# Power.net
KiCad netlist of a schematic drawn in Altium Designer
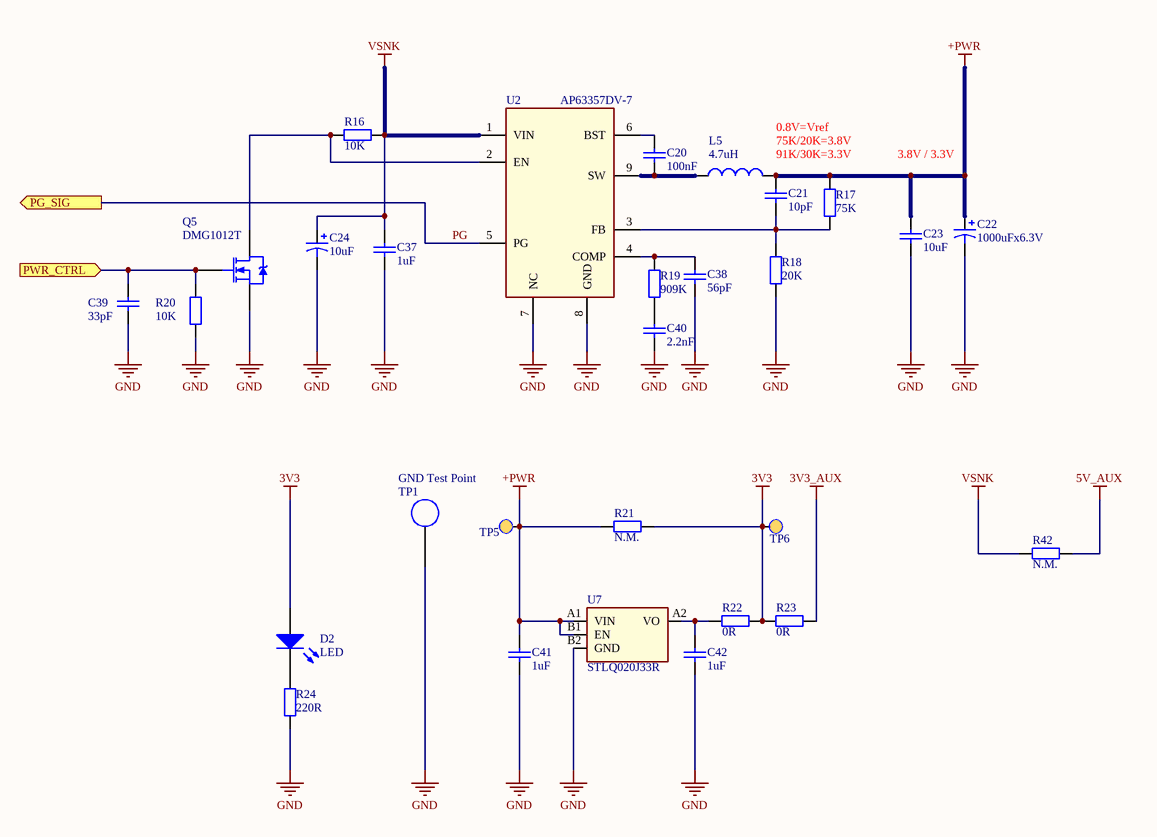
[diagram p0: Power.SchDoc]

(export (version "E")
  (design (tool "Eeschema 10.0.6"))
  (components
    (comp (ref "C20")
      (value "100nF")
      (footprint "C0402")
      (description "Capacitor (Semiconductor SIM Model)")
      (fields
        (field (name "MANUFACTURER") "YAGEO")
        (field (name "MANUFACTURER PART NO.") "CC0402KRX7R9BB104")
      )
      (libsource (lib "Miscellaneous Devices") (part "Cap Semi"))
    )
    (comp (ref "C21")
      (value "10pF")
      (footprint "C0402")
      (description "Capacitor (Semiconductor SIM Model)")
      (fields
        (field (name "MANUFACTURER") "YAGEO")
        (field (name "MANUFACTURER PART NO.") "CC0402JRNPO9BN100")
      )
      (libsource (lib "Miscellaneous Devices") (part "Cap Semi"))
    )
    (comp (ref "C22")
      (value "1000uFx6.3V")
      (footprint "7361-38")
      (fields
        (field (name "MANUFACTURER") "AVX")
        (field (name "MANUFACTURER PART NO.") "TPSV108M006R0050")
        (field (name "Comment") "electrolytic capacitor")
      )
      (libsource (lib "Miscellaneous Devices") (part "Cap Pol1"))
    )
    (comp (ref "C23")
      (value "10uF")
      (footprint "C0402")
      (description "Capacitor (Semiconductor SIM Model)")
      (fields
        (field (name "MANUFACTURER") "Samsung Electronics")
        (field (name "MANUFACTURER PART NO.") "CL05A106MP5NUNC")
      )
      (libsource (lib "Miscellaneous Devices") (part "Cap Semi"))
    )
    (comp (ref "C24")
      (value "10uF")
      (footprint "Case-B")
      (fields
        (field (name "MANUFACTURER") "AVX")
        (field (name "MANUFACTURER PART NO.") "TCJB106M025R0100")
        (field (name "Comment") "electrolytic capacitor")
      )
      (libsource (lib "Miscellaneous Devices") (part "Cap Pol1"))
    )
    (comp (ref "C37")
      (value "1uF")
      (footprint "C0402")
      (description "Capacitor (Semiconductor SIM Model)")
      (fields
        (field (name "MANUFACTURER") "muRata")
        (field (name "MANUFACTURER PART NO.") "GRM155R61E105KA12D")
      )
      (libsource (lib "Miscellaneous Devices") (part "Cap Semi"))
    )
    (comp (ref "C38")
      (value "56pF")
      (footprint "C0402")
      (description "Capacitor (Semiconductor SIM Model)")
      (fields
        (field (name "MANUFACTURER") "YAGEO")
        (field (name "MANUFACTURER PART NO.") "CC0402JRNPO9BN560")
      )
      (libsource (lib "Miscellaneous Devices") (part "Cap Semi"))
    )
    (comp (ref "C39")
      (value "33pF")
      (footprint "C0402")
      (description "Capacitor (Semiconductor SIM Model)")
      (fields (field (name "MANUFACTURER") "AVX") (field (name "MANUFACTURER PART NO.") "04025A330JAT2A"))
      (libsource (lib "Miscellaneous Devices") (part "Cap Semi"))
    )
    (comp (ref "C40")
      (value "2.2nF")
      (footprint "C0402")
      (description "Capacitor (Semiconductor SIM Model)")
      (fields
        (field (name "MANUFACTURER") "YAGEO")
        (field (name "MANUFACTURER PART NO.") "CC0402KPX7R9BB222")
      )
      (libsource (lib "Miscellaneous Devices") (part "Cap Semi"))
    )
    (comp (ref "C41")
      (value "1uF")
      (footprint "C0402")
      (description "Capacitor (Semiconductor SIM Model)")
      (fields
        (field (name "MANUFACTURER") "muRata")
        (field (name "MANUFACTURER PART NO.") "GRM155R61E105KA12D")
      )
      (libsource (lib "Miscellaneous Devices") (part "Cap Semi"))
    )
    (comp (ref "C42")
      (value "1uF")
      (footprint "C0402")
      (description "Capacitor (Semiconductor SIM Model)")
      (fields
        (field (name "MANUFACTURER") "muRata")
        (field (name "MANUFACTURER PART NO.") "GRM155R61E105KA12D")
      )
      (libsource (lib "Miscellaneous Devices") (part "Cap Semi"))
    )
    (comp (ref "D2")
      (value "LED")
      (footprint "PICOLED")
      (description "Typical SMD LED")
      (fields
        (field (name "MANUFACTURER") "OSRAM")
        (field (name "MANUFACTURER PART NO.") "LTQH9G-Q2OO-25-2Z4Y-5-R18")
      )
      (libsource (lib "Miscellaneous Devices") (part "LED2"))
    )
    (comp (ref "L5")
      (value "4.7uH")
      (footprint "CHILSIN_5.4x5.7")
      (description "Inductor")
      (fields
        (field (name "MANUFACTURER") "CHILISIN")
        (field (name "MANUFACTURER PART NO.") "BMRA000505204R7MA1")
      )
      (libsource (lib "Miscellaneous Devices") (part "Inductor"))
    )
    (comp (ref "Q5")
      (value "DMG1012T")
      (footprint "SOT-523_custom")
      (description "N-Channel Power MOSFET")
      (fields (field (name "MANUFACTURER") "Diodes Inc.") (field (name "MANUFACTURER PART NO.") "DMG1012T-7"))
      (libsource (lib "Miscellaneous Devices") (part "NMOS-2"))
    )
    (comp (ref "R16")
      (value "10K")
      (footprint "R0402")
      (fields
        (field (name "MANUFACTURER") "ASJ")
        (field (name "MANUFACTURER PART NO.") "CR10-103-JK")
        (field (name "Comment") "Res2")
      )
      (libsource (lib "") (part "Res2_3"))
    )
    (comp (ref "R17")
      (value "75K")
      (footprint "R0402")
      (fields
        (field (name "MANUFACTURER") "YAGEO")
        (field (name "MANUFACTURER PART NO.") "RC0402JR-0775KL")
        (field (name "Comment") "Res2")
      )
      (libsource (lib "Miscellaneous Devices") (part "Res2"))
    )
    (comp (ref "R18")
      (value "20K")
      (footprint "R0402")
      (fields
        (field (name "MANUFACTURER") "YAGEO")
        (field (name "MANUFACTURER PART NO.") "AC0402JR-0720KL")
        (field (name "Comment") "Res2")
      )
      (libsource (lib "Miscellaneous Devices") (part "Res2"))
    )
    (comp (ref "R19")
      (value "909K")
      (footprint "R0402")
      (fields
        (field (name "MANUFACTURER") "ASJ")
        (field (name "MANUFACTURER PART NO.") "RC0402FR-07909KL")
        (field (name "Comment") "Res2")
      )
      (libsource (lib "Miscellaneous Devices") (part "Res2"))
    )
    (comp (ref "R20")
      (value "10K")
      (footprint "R0402")
      (fields
        (field (name "MANUFACTURER") "ASJ")
        (field (name "MANUFACTURER PART NO.") "CR10-103-JK")
        (field (name "Comment") "Res2")
      )
      (libsource (lib "") (part "Res2_2"))
    )
    (comp (ref "R21")
      (value "N.M.")
      (footprint "R0402")
      (fields
        (field (name "MANUFACTURER") "YAGEO")
        (field (name "MANUFACTURER PART NO.") "RC0402FR-070RL")
        (field (name "Comment") "Res2")
      )
      (libsource (lib "") (part "Res2_1"))
    )
    (comp (ref "R22")
      (value "0R")
      (footprint "R0402")
      (fields
        (field (name "MANUFACTURER") "YAGEO")
        (field (name "MANUFACTURER PART NO.") "RC0402FR-070RL")
        (field (name "Comment") "Res2")
      )
      (libsource (lib "") (part "Res2_1"))
    )
    (comp (ref "R23")
      (value "0R")
      (footprint "R0402")
      (fields
        (field (name "MANUFACTURER") "YAGEO")
        (field (name "MANUFACTURER PART NO.") "RC0402FR-070RL")
        (field (name "Comment") "Res2")
      )
      (libsource (lib "") (part "Res2_1"))
    )
    (comp (ref "R24")
      (value "220R")
      (footprint "R0402")
      (fields
        (field (name "MANUFACTURER") "ASJ")
        (field (name "MANUFACTURER PART NO.") "CR10-221-JK")
        (field (name "Comment") "Res2")
      )
      (libsource (lib "Miscellaneous Devices") (part "Res2"))
    )
    (comp (ref "R42")
      (value "N.M.")
      (footprint "R1206")
      (fields
        (field (name "MANUFACTURER") "YAGEO")
        (field (name "MANUFACTURER PART NO.") "RC0402FR-070RL")
        (field (name "Comment") "Res2")
      )
      (libsource (lib "") (part "Res2_1"))
    )
    (comp (ref "TP1")
      (value "GND Test Point")
      (footprint "5019_keystone")
      (description "SMD Test Point")
      (fields
        (field (name "MANUFACTURER") "Keystone Electrincs")
        (field (name "MANUFACTURER PART NO.") "5019")
      )
      (libsource (lib "test_point") (part "5019"))
    )
    (comp (ref "TP5")
      (value "Test_Point")
      (footprint "TEST_POINT")
      (description "Test Point")
      (libsource (lib "Test Point") (part "Test_Point"))
    )
    (comp (ref "TP6")
      (value "Test_Point")
      (footprint "TEST_POINT")
      (description "Test Point")
      (libsource (lib "Test Point") (part "Test_Point"))
    )
    (comp (ref "U2")
      (value "AP63357DV-7")
      (footprint "V-DFN3020-13")
      (description "3.8V TO 32VINPUT, 3.5A Low IQ Synchronous Buck with Enhanced EMI Reduction")
      (fields (field (name "MANUFACTURER") "Diodes Inc."))
      (libsource (lib "AP63356") (part "AP63356"))
    )
    (comp (ref "U7")
      (value "STLQ020J33R")
      (footprint "Flip-Chip4")
      (description "LDO")
      (fields (field (name "MANUFACTURER") "STMicroelectronics"))
      (libsource (lib "RUTLEO") (part "STLQ020"))
    )
  )
  (nets
    (net (code "1") (name "+PWR") (class "Default")
      (node (ref "C21") (pin "2") (pinfunction "2_2") (pintype "passive"))
      (node (ref "C22") (pin "1") (pinfunction "1_1") (pintype "passive"))
      (node (ref "C23") (pin "2") (pinfunction "2_2") (pintype "passive"))
      (node (ref "C41") (pin "1") (pinfunction "1_1") (pintype "passive"))
      (node (ref "L5") (pin "2") (pinfunction "2_2") (pintype "passive"))
      (node (ref "R17") (pin "1") (pinfunction "1_1") (pintype "passive"))
      (node (ref "R21") (pin "2") (pinfunction "2_2") (pintype "passive"))
      (node (ref "TP5") (pin "0") (pinfunction "0_0") (pintype "passive"))
      (node (ref "U7") (pin "A1") (pinfunction "VIN_A1") (pintype "passive"))
      (node (ref "U7") (pin "B1") (pinfunction "EN_B1") (pintype "passive"))
    )
    (net (code "2") (name "/PG") (class "Default")
      (node (ref "U2") (pin "5") (pinfunction "PG_5") (pintype "passive"))
    )
    (net (code "3") (name "/PWR_CTRL") (class "Default")
      (node (ref "C39") (pin "1") (pinfunction "1_1") (pintype "passive"))
      (node (ref "Q5") (pin "1") (pinfunction "G_1") (pintype "passive"))
      (node (ref "R20") (pin "2") (pinfunction "2_2") (pintype "passive"))
    )
    (net (code "4") (name "3V3") (class "Default")
      (node (ref "D2") (pin "1") (pinfunction "A_1") (pintype "passive"))
      (node (ref "R21") (pin "1") (pinfunction "1_1") (pintype "passive"))
      (node (ref "R22") (pin "1") (pinfunction "1_1") (pintype "passive"))
      (node (ref "R23") (pin "2") (pinfunction "2_2") (pintype "passive"))
      (node (ref "TP6") (pin "0") (pinfunction "0_0") (pintype "passive"))
    )
    (net (code "5") (name "3V3_AUX") (class "Default")
      (node (ref "R23") (pin "1") (pinfunction "1_1") (pintype "passive"))
    )
    (net (code "6") (name "5V_AUX") (class "Default")
      (node (ref "R42") (pin "1") (pinfunction "1_1") (pintype "passive"))
    )
    (net (code "7") (name "GND") (class "Default")
      (node (ref "C22") (pin "2") (pinfunction "2_2") (pintype "passive"))
      (node (ref "C23") (pin "1") (pinfunction "1_1") (pintype "passive"))
      (node (ref "C24") (pin "2") (pinfunction "2_2") (pintype "passive"))
      (node (ref "C37") (pin "1") (pinfunction "1_1") (pintype "passive"))
      (node (ref "C38") (pin "1") (pinfunction "1_1") (pintype "passive"))
      (node (ref "C39") (pin "2") (pinfunction "2_2") (pintype "passive"))
      (node (ref "C40") (pin "1") (pinfunction "1_1") (pintype "passive"))
      (node (ref "C41") (pin "2") (pinfunction "2_2") (pintype "passive"))
      (node (ref "C42") (pin "2") (pinfunction "2_2") (pintype "passive"))
      (node (ref "Q5") (pin "3") (pinfunction "S_3") (pintype "passive"))
      (node (ref "R18") (pin "2") (pinfunction "2_2") (pintype "passive"))
      (node (ref "R20") (pin "1") (pinfunction "1_1") (pintype "passive"))
      (node (ref "R24") (pin "2") (pinfunction "2_2") (pintype "passive"))
      (node (ref "TP1") (pin "1") (pinfunction "1_1") (pintype "passive"))
      (node (ref "U2") (pin "7") (pinfunction "NC_7") (pintype "passive"))
      (node (ref "U2") (pin "8") (pinfunction "GND_8") (pintype "passive"))
      (node (ref "U7") (pin "B2") (pinfunction "GND_B2") (pintype "passive"))
    )
    (net (code "8") (name "Net-(C40-Pad2)") (class "Default")
      (node (ref "C40") (pin "2") (pinfunction "2_2") (pintype "passive"))
      (node (ref "R19") (pin "2") (pinfunction "2_2") (pintype "passive"))
    )
    (net (code "9") (name "Net-(D2-K)") (class "Default")
      (node (ref "D2") (pin "2") (pinfunction "K_2") (pintype "passive"))
      (node (ref "R24") (pin "1") (pinfunction "1_1") (pintype "passive"))
    )
    (net (code "10") (name "Net-(Q5-D)") (class "Default")
      (node (ref "Q5") (pin "2") (pinfunction "D_2") (pintype "passive"))
      (node (ref "R16") (pin "1") (pinfunction "1_1") (pintype "passive"))
      (node (ref "U2") (pin "2") (pinfunction "EN_2") (pintype "passive"))
    )
    (net (code "11") (name "Net-(U2-BST)") (class "Default")
      (node (ref "C20") (pin "1") (pinfunction "1_1") (pintype "passive"))
      (node (ref "U2") (pin "6") (pinfunction "BST_6") (pintype "passive"))
    )
    (net (code "12") (name "Net-(U2-COMP)") (class "Default")
      (node (ref "C38") (pin "2") (pinfunction "2_2") (pintype "passive"))
      (node (ref "R19") (pin "1") (pinfunction "1_1") (pintype "passive"))
      (node (ref "U2") (pin "4") (pinfunction "COMP_4") (pintype "passive"))
    )
    (net (code "13") (name "Net-(U2-FB)") (class "Default")
      (node (ref "C21") (pin "1") (pinfunction "1_1") (pintype "passive"))
      (node (ref "R17") (pin "2") (pinfunction "2_2") (pintype "passive"))
      (node (ref "R18") (pin "1") (pinfunction "1_1") (pintype "passive"))
      (node (ref "U2") (pin "3") (pinfunction "FB_3") (pintype "passive"))
    )
    (net (code "14") (name "Net-(U2-SW)") (class "Default")
      (node (ref "C20") (pin "2") (pinfunction "2_2") (pintype "passive"))
      (node (ref "L5") (pin "1") (pinfunction "1_1") (pintype "passive"))
      (node (ref "U2") (pin "9") (pinfunction "SW_9") (pintype "passive"))
    )
    (net (code "15") (name "Net-(U7-VO)") (class "Default")
      (node (ref "C42") (pin "1") (pinfunction "1_1") (pintype "passive"))
      (node (ref "R22") (pin "2") (pinfunction "2_2") (pintype "passive"))
      (node (ref "U7") (pin "A2") (pinfunction "VO_A2") (pintype "passive"))
    )
    (net (code "16") (name "VSNK") (class "Default")
      (node (ref "C24") (pin "1") (pinfunction "1_1") (pintype "passive"))
      (node (ref "C37") (pin "2") (pinfunction "2_2") (pintype "passive"))
      (node (ref "R16") (pin "2") (pinfunction "2_2") (pintype "passive"))
      (node (ref "R42") (pin "2") (pinfunction "2_2") (pintype "passive"))
      (node (ref "U2") (pin "1") (pinfunction "VIN_1") (pintype "passive"))
    )
  )
)
